# Domino_LED_No_Teardrop.net
KiCad netlist of a schematic drawn in EAGLE
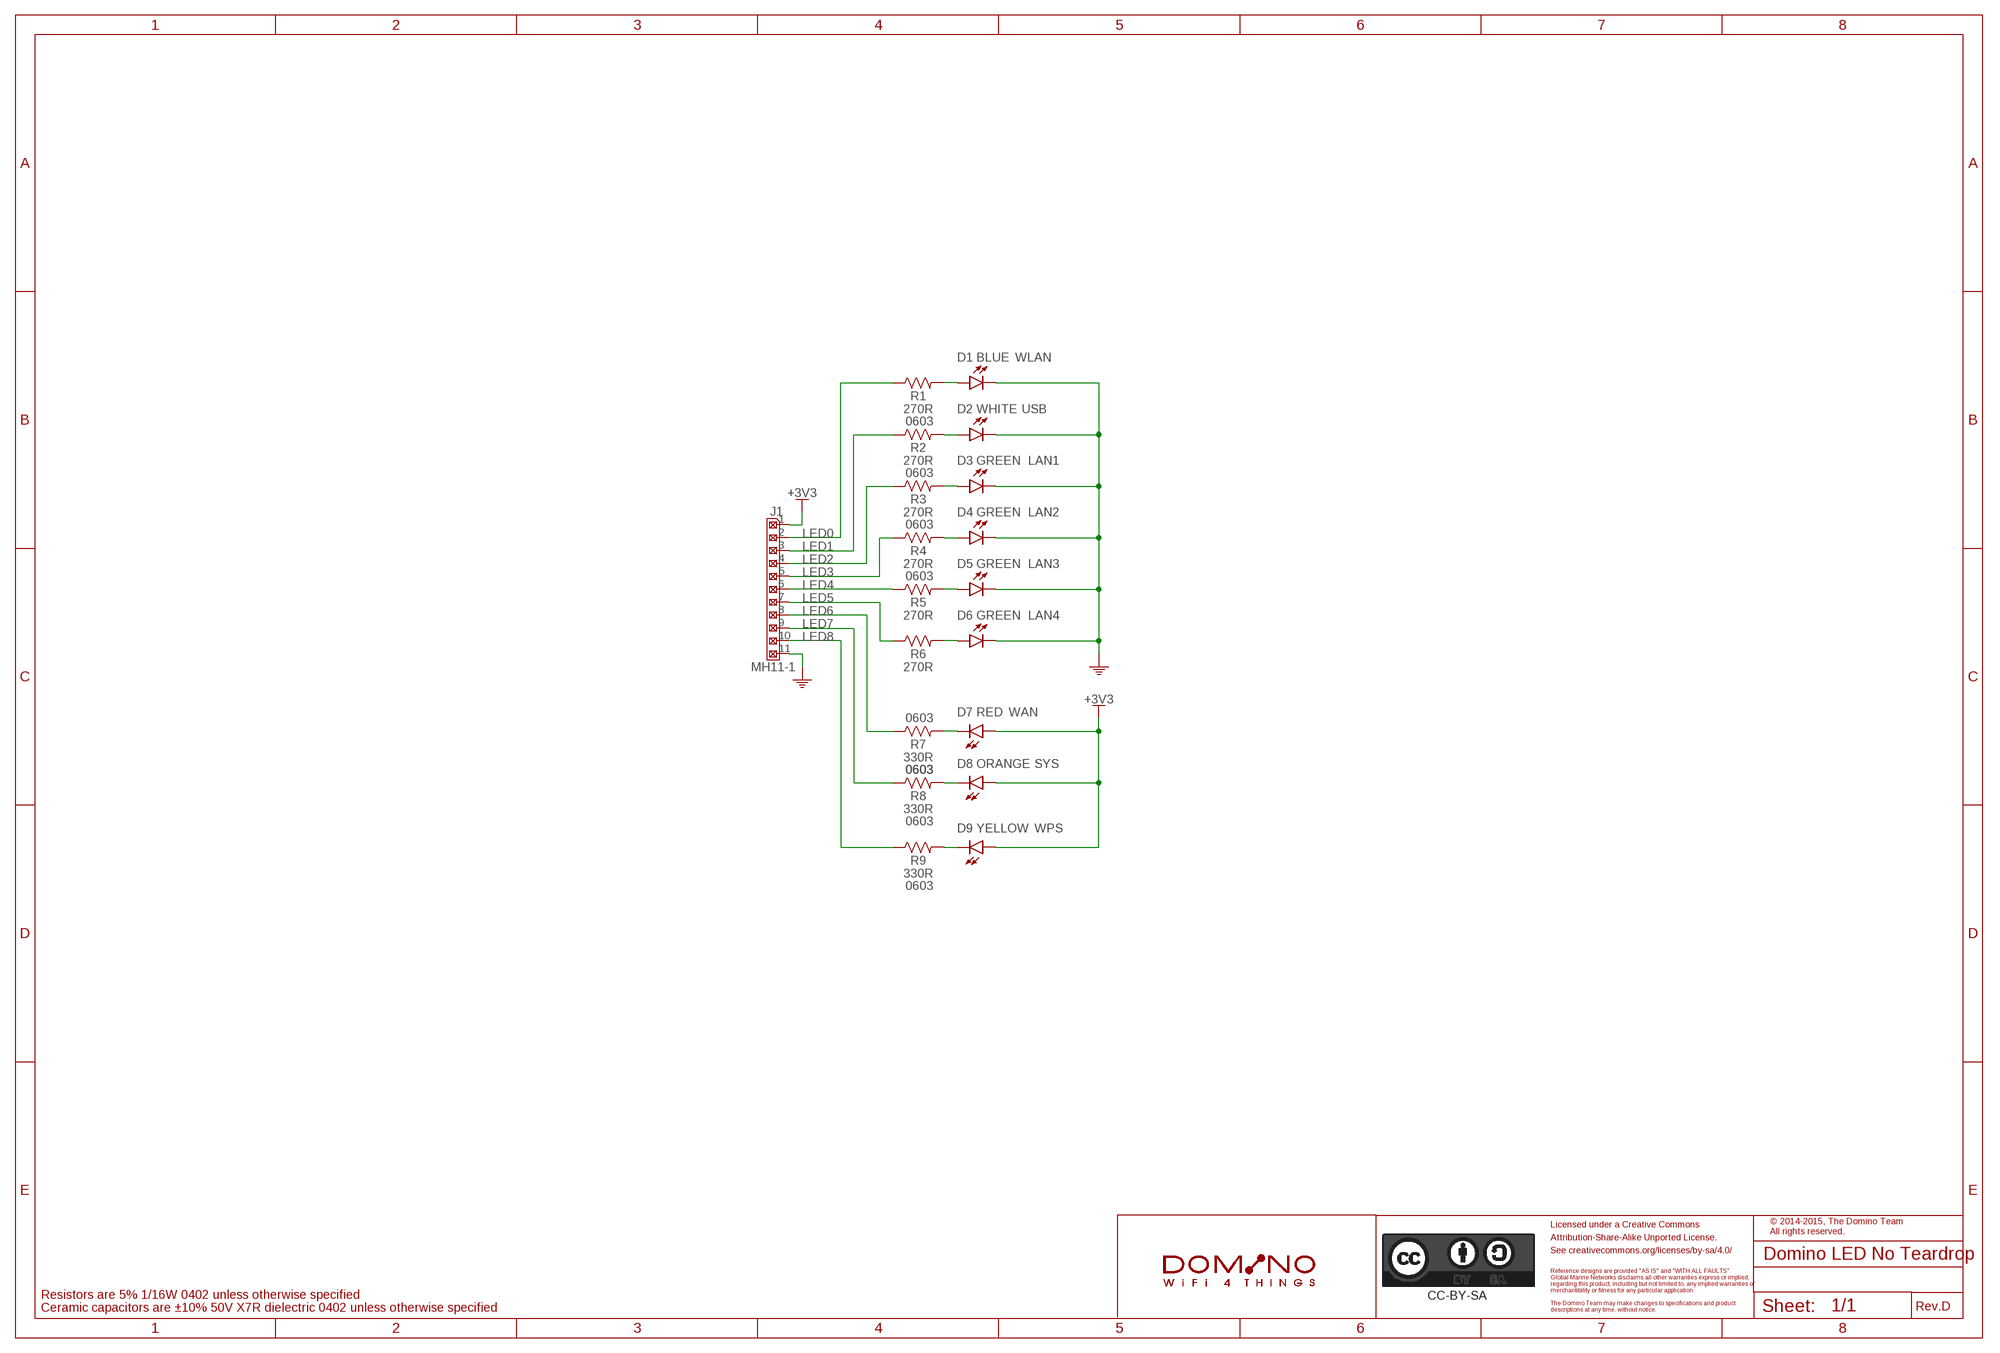
[diagram p0: schematic, sheet 1]

(export (version "E")
  (design (tool "Eeschema 10.0.6"))
  (components
    (comp (ref "CC-BY-SA1")
      (value "CC-BY-SA_LOGO")
      (footprint "eagle-import:CC-BY-SA_LOGO")
      (libsource (lib "eagle-import") (part "CC-BY-SA_LOGO"))
    )
    (comp (ref "D1")
      (value "BLUE")
      (footprint "eagle-import:LED0603")
      (fields (field (name "PARTNO") "LED0603-BLUE"))
      (libsource (lib "eagle-import") (part "LED_0603"))
    )
    (comp (ref "D2")
      (value "WHITE")
      (footprint "eagle-import:LED0603")
      (fields (field (name "PARTNO") "LED0603-WHITE"))
      (libsource (lib "eagle-import") (part "LED_0603"))
    )
    (comp (ref "D3")
      (value "GREEN")
      (footprint "eagle-import:LED0603")
      (fields (field (name "PARTNO") "LED0603-GREEN"))
      (libsource (lib "eagle-import") (part "LED_0603"))
    )
    (comp (ref "D4")
      (value "GREEN")
      (footprint "eagle-import:LED0603")
      (fields (field (name "PARTNO") "LED0603-GREEN"))
      (libsource (lib "eagle-import") (part "LED_0603"))
    )
    (comp (ref "D5")
      (value "GREEN")
      (footprint "eagle-import:LED0603")
      (fields (field (name "PARTNO") "LED0603-GREEN"))
      (libsource (lib "eagle-import") (part "LED_0603"))
    )
    (comp (ref "D6")
      (value "GREEN")
      (footprint "eagle-import:LED0603")
      (fields (field (name "PARTNO") "LED0603-GREEN"))
      (libsource (lib "eagle-import") (part "LED_0603"))
    )
    (comp (ref "D7")
      (value "RED")
      (footprint "eagle-import:LED0603")
      (fields (field (name "PARTNO") "LED0603-RED"))
      (libsource (lib "eagle-import") (part "LED_0603"))
    )
    (comp (ref "D8")
      (value "ORANGE")
      (footprint "eagle-import:LED0603")
      (fields (field (name "PARTNO") "LED0603-ORANGE"))
      (libsource (lib "eagle-import") (part "LED_0603"))
    )
    (comp (ref "D9")
      (value "YELLOW")
      (footprint "eagle-import:LED0603")
      (fields (field (name "PARTNO") "LED0603-YELLOW"))
      (libsource (lib "eagle-import") (part "LED_0603"))
    )
    (comp (ref "J1")
      (value "MH11-1")
      (footprint "eagle-import:MH11-1-0.1")
      (fields (field (name "PARTNO") "MH11-1-0.1"))
      (libsource (lib "eagle-import") (part "MH11-1"))
    )
    (comp (ref "R1")
      (value "270R")
      (footprint "eagle-import:R0603")
      (fields (field (name "SIZE") "0603") (field (name "PARTNO") "R0603_270R_5%_125mW"))
      (libsource (lib "eagle-import") (part "RES_0603"))
    )
    (comp (ref "R2")
      (value "270R")
      (footprint "eagle-import:R0603")
      (fields (field (name "SIZE") "0603") (field (name "PARTNO") "R0603_270R_5%_125mW"))
      (libsource (lib "eagle-import") (part "RES_0603"))
    )
    (comp (ref "R3")
      (value "270R")
      (footprint "eagle-import:R0603")
      (fields (field (name "SIZE") "0603") (field (name "PARTNO") "R0603_270R_5%_125mW"))
      (libsource (lib "eagle-import") (part "RES_0603"))
    )
    (comp (ref "R4")
      (value "270R")
      (footprint "eagle-import:R0603")
      (fields (field (name "SIZE") "0603") (field (name "PARTNO") "R0603_270R_5%_125mW"))
      (libsource (lib "eagle-import") (part "RES_0603"))
    )
    (comp (ref "R5")
      (value "270R")
      (footprint "eagle-import:R0603")
      (fields (field (name "SIZE") "0603") (field (name "PARTNO") "R0603_270R_5%_125mW"))
      (libsource (lib "eagle-import") (part "RES_0603"))
    )
    (comp (ref "R6")
      (value "270R")
      (footprint "eagle-import:R0603")
      (fields (field (name "SIZE") "0603") (field (name "PARTNO") "R0603_270R_5%_125mW"))
      (libsource (lib "eagle-import") (part "RES_0603"))
    )
    (comp (ref "R7")
      (value "330R")
      (footprint "eagle-import:R0603")
      (fields (field (name "SIZE") "0603") (field (name "PARTNO") "R0603_330R_5%_125mW"))
      (libsource (lib "eagle-import") (part "RES_0603"))
    )
    (comp (ref "R8")
      (value "330R")
      (footprint "eagle-import:R0603")
      (fields (field (name "SIZE") "0603") (field (name "PARTNO") "R0603_330R_5%_125mW"))
      (libsource (lib "eagle-import") (part "RES_0603"))
    )
    (comp (ref "R9")
      (value "330R")
      (footprint "eagle-import:R0603")
      (fields (field (name "SIZE") "0603") (field (name "PARTNO") "R0603_330R_5%_125mW"))
      (libsource (lib "eagle-import") (part "RES_0603"))
    )
    (comp (ref "U$4")
      (value "DOMINO_LOGO")
      (footprint "eagle-import:DOMINO_LOGO")
      (libsource (lib "eagle-import") (part "DOMINO_LOGO"))
    )
  )
  (nets
    (net (code "1") (name "+3V3") (class "Default")
      (node (ref "D7") (pin "2") (pinfunction "A_2") (pintype "passive"))
      (node (ref "D8") (pin "2") (pinfunction "A_2") (pintype "passive"))
      (node (ref "D9") (pin "2") (pinfunction "A_2") (pintype "passive"))
      (node (ref "J1") (pin "1") (pinfunction "1_1") (pintype "passive"))
    )
    (net (code "2") (name "/LED0") (class "Default")
      (node (ref "J1") (pin "2") (pinfunction "2_2") (pintype "passive"))
      (node (ref "R1") (pin "1") (pinfunction "1_1") (pintype "passive"))
    )
    (net (code "3") (name "/LED1") (class "Default")
      (node (ref "J1") (pin "3") (pinfunction "3_3") (pintype "passive"))
      (node (ref "R2") (pin "1") (pinfunction "1_1") (pintype "passive"))
    )
    (net (code "4") (name "/LED2") (class "Default")
      (node (ref "J1") (pin "4") (pinfunction "4_4") (pintype "passive"))
      (node (ref "R3") (pin "1") (pinfunction "1_1") (pintype "passive"))
    )
    (net (code "5") (name "/LED3") (class "Default")
      (node (ref "J1") (pin "5") (pinfunction "5_5") (pintype "passive"))
      (node (ref "R4") (pin "1") (pinfunction "1_1") (pintype "passive"))
    )
    (net (code "6") (name "/LED4") (class "Default")
      (node (ref "J1") (pin "6") (pinfunction "6_6") (pintype "passive"))
      (node (ref "R5") (pin "1") (pinfunction "1_1") (pintype "passive"))
    )
    (net (code "7") (name "/LED5") (class "Default")
      (node (ref "J1") (pin "7") (pinfunction "7_7") (pintype "passive"))
      (node (ref "R6") (pin "1") (pinfunction "1_1") (pintype "passive"))
    )
    (net (code "8") (name "/LED6") (class "Default")
      (node (ref "J1") (pin "8") (pinfunction "8_8") (pintype "passive"))
      (node (ref "R7") (pin "1") (pinfunction "1_1") (pintype "passive"))
    )
    (net (code "9") (name "/LED7") (class "Default")
      (node (ref "J1") (pin "9") (pinfunction "9_9") (pintype "passive"))
      (node (ref "R8") (pin "1") (pinfunction "1_1") (pintype "passive"))
    )
    (net (code "10") (name "/LED8") (class "Default")
      (node (ref "J1") (pin "10") (pinfunction "10_10") (pintype "passive"))
      (node (ref "R9") (pin "1") (pinfunction "1_1") (pintype "passive"))
    )
    (net (code "11") (name "GND") (class "Default")
      (node (ref "D1") (pin "1") (pinfunction "C_1") (pintype "passive"))
      (node (ref "D2") (pin "1") (pinfunction "C_1") (pintype "passive"))
      (node (ref "D3") (pin "1") (pinfunction "C_1") (pintype "passive"))
      (node (ref "D4") (pin "1") (pinfunction "C_1") (pintype "passive"))
      (node (ref "D5") (pin "1") (pinfunction "C_1") (pintype "passive"))
      (node (ref "D6") (pin "1") (pinfunction "C_1") (pintype "passive"))
      (node (ref "J1") (pin "11") (pinfunction "11_11") (pintype "passive"))
    )
    (net (code "12") (name "Net-(D1-A)") (class "Default")
      (node (ref "D1") (pin "2") (pinfunction "A_2") (pintype "passive"))
      (node (ref "R1") (pin "2") (pinfunction "2_2") (pintype "passive"))
    )
    (net (code "13") (name "Net-(D2-A)") (class "Default")
      (node (ref "D2") (pin "2") (pinfunction "A_2") (pintype "passive"))
      (node (ref "R2") (pin "2") (pinfunction "2_2") (pintype "passive"))
    )
    (net (code "14") (name "Net-(D3-A)") (class "Default")
      (node (ref "D3") (pin "2") (pinfunction "A_2") (pintype "passive"))
      (node (ref "R3") (pin "2") (pinfunction "2_2") (pintype "passive"))
    )
    (net (code "15") (name "Net-(D4-A)") (class "Default")
      (node (ref "D4") (pin "2") (pinfunction "A_2") (pintype "passive"))
      (node (ref "R4") (pin "2") (pinfunction "2_2") (pintype "passive"))
    )
    (net (code "16") (name "Net-(D5-A)") (class "Default")
      (node (ref "D5") (pin "2") (pinfunction "A_2") (pintype "passive"))
      (node (ref "R5") (pin "2") (pinfunction "2_2") (pintype "passive"))
    )
    (net (code "17") (name "Net-(D6-A)") (class "Default")
      (node (ref "D6") (pin "2") (pinfunction "A_2") (pintype "passive"))
      (node (ref "R6") (pin "2") (pinfunction "2_2") (pintype "passive"))
    )
    (net (code "18") (name "Net-(D7-C)") (class "Default")
      (node (ref "D7") (pin "1") (pinfunction "C_1") (pintype "passive"))
      (node (ref "R7") (pin "2") (pinfunction "2_2") (pintype "passive"))
    )
    (net (code "19") (name "Net-(D8-C)") (class "Default")
      (node (ref "D8") (pin "1") (pinfunction "C_1") (pintype "passive"))
      (node (ref "R8") (pin "2") (pinfunction "2_2") (pintype "passive"))
    )
    (net (code "20") (name "Net-(D9-C)") (class "Default")
      (node (ref "D9") (pin "1") (pinfunction "C_1") (pintype "passive"))
      (node (ref "R9") (pin "2") (pinfunction "2_2") (pintype "passive"))
    )
  )
)
